# PowerSupply.net
KiCad netlist of a schematic drawn in EAGLE
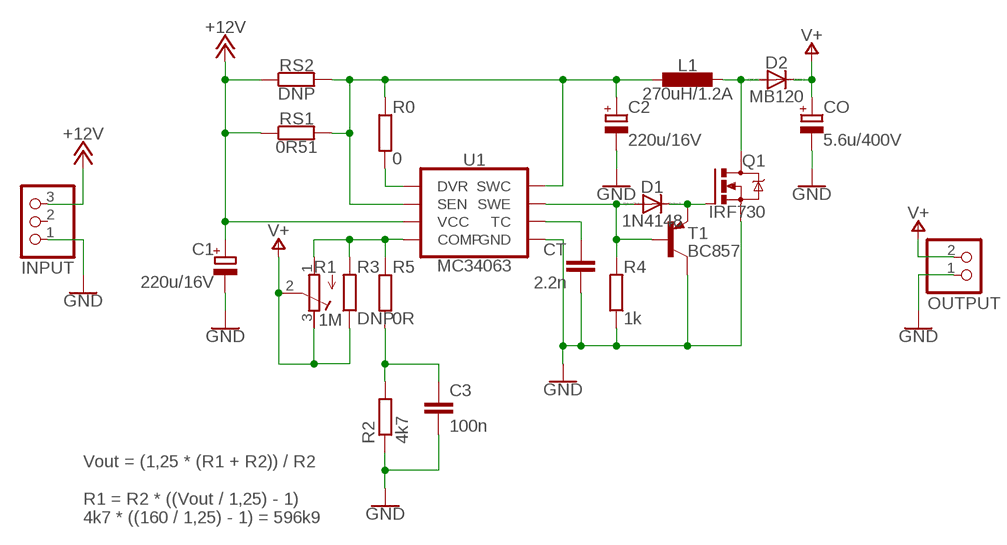
[diagram p0: schematic, sheet 1]

(export (version "E")
  (design (tool "Eeschema 10.0.6"))
  (components
    (comp (ref "C1")
      (value "220u/16V")
      (footprint "eagle-import:140CLH-0810")
      (libsource (lib "eagle-import") (part "CPOL-EU140CLH-0810"))
    )
    (comp (ref "C2")
      (value "220u/16V")
      (footprint "eagle-import:140CLH-0810")
      (libsource (lib "eagle-import") (part "CPOL-EU140CLH-0810"))
    )
    (comp (ref "C3")
      (value "100n")
      (footprint "eagle-import:C0603K")
      (libsource (lib "eagle-import") (part "C-EUC0603K"))
    )
    (comp (ref "CO")
      (value "5.6u/400V")
      (footprint "eagle-import:153CLV-1010")
      (libsource (lib "eagle-import") (part "CPOL-EU153CLV-1010"))
    )
    (comp (ref "CT")
      (value "2.2n")
      (footprint "eagle-import:C0603K")
      (libsource (lib "eagle-import") (part "C-EUC0603K"))
    )
    (comp (ref "D1")
      (value "1N4148")
      (footprint "eagle-import:SOD323-W")
      (libsource (lib "eagle-import") (part "DIODE-SOD323-W"))
    )
    (comp (ref "D2")
      (value "MB120")
      (footprint "eagle-import:DO214AA")
      (libsource (lib "eagle-import") (part "DIODE-DO214AA"))
    )
    (comp (ref "INPUT")
      (value "PINHD-1X3")
      (footprint "eagle-import:1X03")
      (libsource (lib "eagle-import") (part "PINHD-1X3"))
    )
    (comp (ref "L1")
      (value "270uH/1.2A")
      (footprint "eagle-import:TC-PIS4728")
      (libsource (lib "eagle-import") (part "TC-PIS4728"))
    )
    (comp (ref "OUTPUT")
      (value "PINHD-1X2")
      (footprint "eagle-import:1X02")
      (libsource (lib "eagle-import") (part "PINHD-1X2"))
    )
    (comp (ref "Q1")
      (value "IRF730")
      (footprint "eagle-import:TO220BV")
      (fields (field (name "SPICEPREFIX") "Q"))
      (libsource (lib "eagle-import") (part "IRF740"))
    )
    (comp (ref "R0")
      (value "0")
      (footprint "eagle-import:R0603")
      (libsource (lib "eagle-import") (part "R-EU_R0603"))
    )
    (comp (ref "R1")
      (value "1M")
      (footprint "eagle-import:RTRIM64W")
      (libsource (lib "eagle-import") (part "R-TRIMM64W"))
    )
    (comp (ref "R2")
      (value "4k7")
      (footprint "eagle-import:R0603")
      (libsource (lib "eagle-import") (part "R-EU_R0603"))
    )
    (comp (ref "R3")
      (value "DNP")
      (footprint "eagle-import:R0603")
      (libsource (lib "eagle-import") (part "R-EU_R0603"))
    )
    (comp (ref "R4")
      (value "1k")
      (footprint "eagle-import:R0603")
      (libsource (lib "eagle-import") (part "R-EU_R0603"))
    )
    (comp (ref "R5")
      (value "0R")
      (footprint "eagle-import:R0603")
      (libsource (lib "eagle-import") (part "R-EU_R0603"))
    )
    (comp (ref "RS1")
      (value "0R51")
      (footprint "eagle-import:R2512")
      (libsource (lib "eagle-import") (part "R-EU_R2512"))
    )
    (comp (ref "RS2")
      (value "DNP")
      (footprint "eagle-import:R2512")
      (libsource (lib "eagle-import") (part "R-EU_R2512"))
    )
    (comp (ref "T1")
      (value "BC857")
      (footprint "eagle-import:SOT23-BEC")
      (libsource (lib "eagle-import") (part "-PNP-SOT23-BECBC857A"))
    )
    (comp (ref "U1")
      (value "MC34063")
      (footprint "eagle-import:SOIC127P600X175-8")
      (fields (field (name "SPICEPREFIX") "X"))
      (libsource (lib "eagle-import") (part "MC34063"))
    )
  )
  (nets
    (net (code "1") (name "+12V") (class "Default")
      (node (ref "C1") (pin "+") (pinfunction "+_+") (pintype "passive"))
      (node (ref "INPUT") (pin "3") (pinfunction "3_3") (pintype "passive"))
      (node (ref "RS1") (pin "1") (pinfunction "1_1") (pintype "passive"))
      (node (ref "RS2") (pin "1") (pinfunction "1_1") (pintype "passive"))
      (node (ref "U1") (pin "6") (pinfunction "VCC_6") (pintype "bidirectional"))
    )
    (net (code "2") (name "GND") (class "Default")
      (node (ref "C1") (pin "-") (pinfunction "-_-") (pintype "passive"))
      (node (ref "C2") (pin "-") (pinfunction "-_-") (pintype "passive"))
      (node (ref "C3") (pin "2") (pinfunction "2_2") (pintype "passive"))
      (node (ref "CO") (pin "-") (pinfunction "-_-") (pintype "passive"))
      (node (ref "CT") (pin "1") (pinfunction "1_1") (pintype "passive"))
      (node (ref "INPUT") (pin "1") (pinfunction "1_1") (pintype "passive"))
      (node (ref "OUTPUT") (pin "1") (pinfunction "1_1") (pintype "passive"))
      (node (ref "Q1") (pin "S") (pinfunction "S_S") (pintype "passive"))
      (node (ref "R2") (pin "1") (pinfunction "1_1") (pintype "passive"))
      (node (ref "R4") (pin "1") (pinfunction "1_1") (pintype "passive"))
      (node (ref "T1") (pin "C") (pinfunction "C_C") (pintype "passive"))
      (node (ref "U1") (pin "4") (pinfunction "GND_4") (pintype "bidirectional"))
    )
    (net (code "3") (name "Net-(C3-Pad1)") (class "Default")
      (node (ref "C3") (pin "1") (pinfunction "1_1") (pintype "passive"))
      (node (ref "R2") (pin "2") (pinfunction "2_2") (pintype "passive"))
      (node (ref "R5") (pin "2") (pinfunction "2_2") (pintype "passive"))
    )
    (net (code "4") (name "Net-(D1-PadC)") (class "Default")
      (node (ref "D1") (pin "C") (pinfunction "C_C") (pintype "passive"))
      (node (ref "Q1") (pin "G") (pinfunction "G_G") (pintype "passive"))
      (node (ref "T1") (pin "E") (pinfunction "E_E") (pintype "passive"))
    )
    (net (code "5") (name "Net-(L1-1)") (class "Default")
      (node (ref "D2") (pin "A") (pinfunction "A_A") (pintype "passive"))
      (node (ref "L1") (pin "P$1") (pinfunction "1_P$1") (pintype "passive"))
      (node (ref "Q1") (pin "D") (pinfunction "D_D") (pintype "passive"))
    )
    (net (code "6") (name "Net-(L1-2)") (class "Default")
      (node (ref "C2") (pin "+") (pinfunction "+_+") (pintype "passive"))
      (node (ref "L1") (pin "P$2") (pinfunction "2_P$2") (pintype "passive"))
      (node (ref "R0") (pin "1") (pinfunction "1_1") (pintype "passive"))
      (node (ref "RS1") (pin "2") (pinfunction "2_2") (pintype "passive"))
      (node (ref "RS2") (pin "2") (pinfunction "2_2") (pintype "passive"))
      (node (ref "U1") (pin "1") (pinfunction "SWC_1") (pintype "bidirectional"))
      (node (ref "U1") (pin "7") (pinfunction "SEN_7") (pintype "bidirectional"))
    )
    (net (code "7") (name "Net-(R1-A)") (class "Default")
      (node (ref "R1") (pin "1") (pinfunction "A_1") (pintype "passive"))
      (node (ref "R3") (pin "2") (pinfunction "2_2") (pintype "passive"))
      (node (ref "R5") (pin "1") (pinfunction "1_1") (pintype "passive"))
      (node (ref "U1") (pin "5") (pinfunction "COMP_5") (pintype "bidirectional"))
    )
    (net (code "8") (name "Net-(U1-DVR)") (class "Default")
      (node (ref "R0") (pin "2") (pinfunction "2_2") (pintype "passive"))
      (node (ref "U1") (pin "8") (pinfunction "DVR_8") (pintype "bidirectional"))
    )
    (net (code "9") (name "Net-(U1-SWE)") (class "Default")
      (node (ref "D1") (pin "A") (pinfunction "A_A") (pintype "passive"))
      (node (ref "R4") (pin "2") (pinfunction "2_2") (pintype "passive"))
      (node (ref "T1") (pin "B") (pinfunction "B_B") (pintype "passive"))
      (node (ref "U1") (pin "2") (pinfunction "SWE_2") (pintype "bidirectional"))
    )
    (net (code "10") (name "Net-(U1-TC)") (class "Default")
      (node (ref "CT") (pin "2") (pinfunction "2_2") (pintype "passive"))
      (node (ref "U1") (pin "3") (pinfunction "TC_3") (pintype "bidirectional"))
    )
    (net (code "11") (name "V+") (class "Default")
      (node (ref "CO") (pin "+") (pinfunction "+_+") (pintype "passive"))
      (node (ref "D2") (pin "C") (pinfunction "C_C") (pintype "passive"))
      (node (ref "OUTPUT") (pin "2") (pinfunction "2_2") (pintype "passive"))
      (node (ref "R1") (pin "2") (pinfunction "S_2") (pintype "passive"))
      (node (ref "R1") (pin "3") (pinfunction "E_3") (pintype "passive"))
      (node (ref "R3") (pin "1") (pinfunction "1_1") (pintype "passive"))
    )
    (net (code "12") (name "unconnected-(INPUT-Pad2)") (class "Default")
      (node (ref "INPUT") (pin "2") (pinfunction "2_2") (pintype "passive"))
    )
  )
)
